# Base_IC.net
KiCad netlist of a schematic drawn in Altium Designer
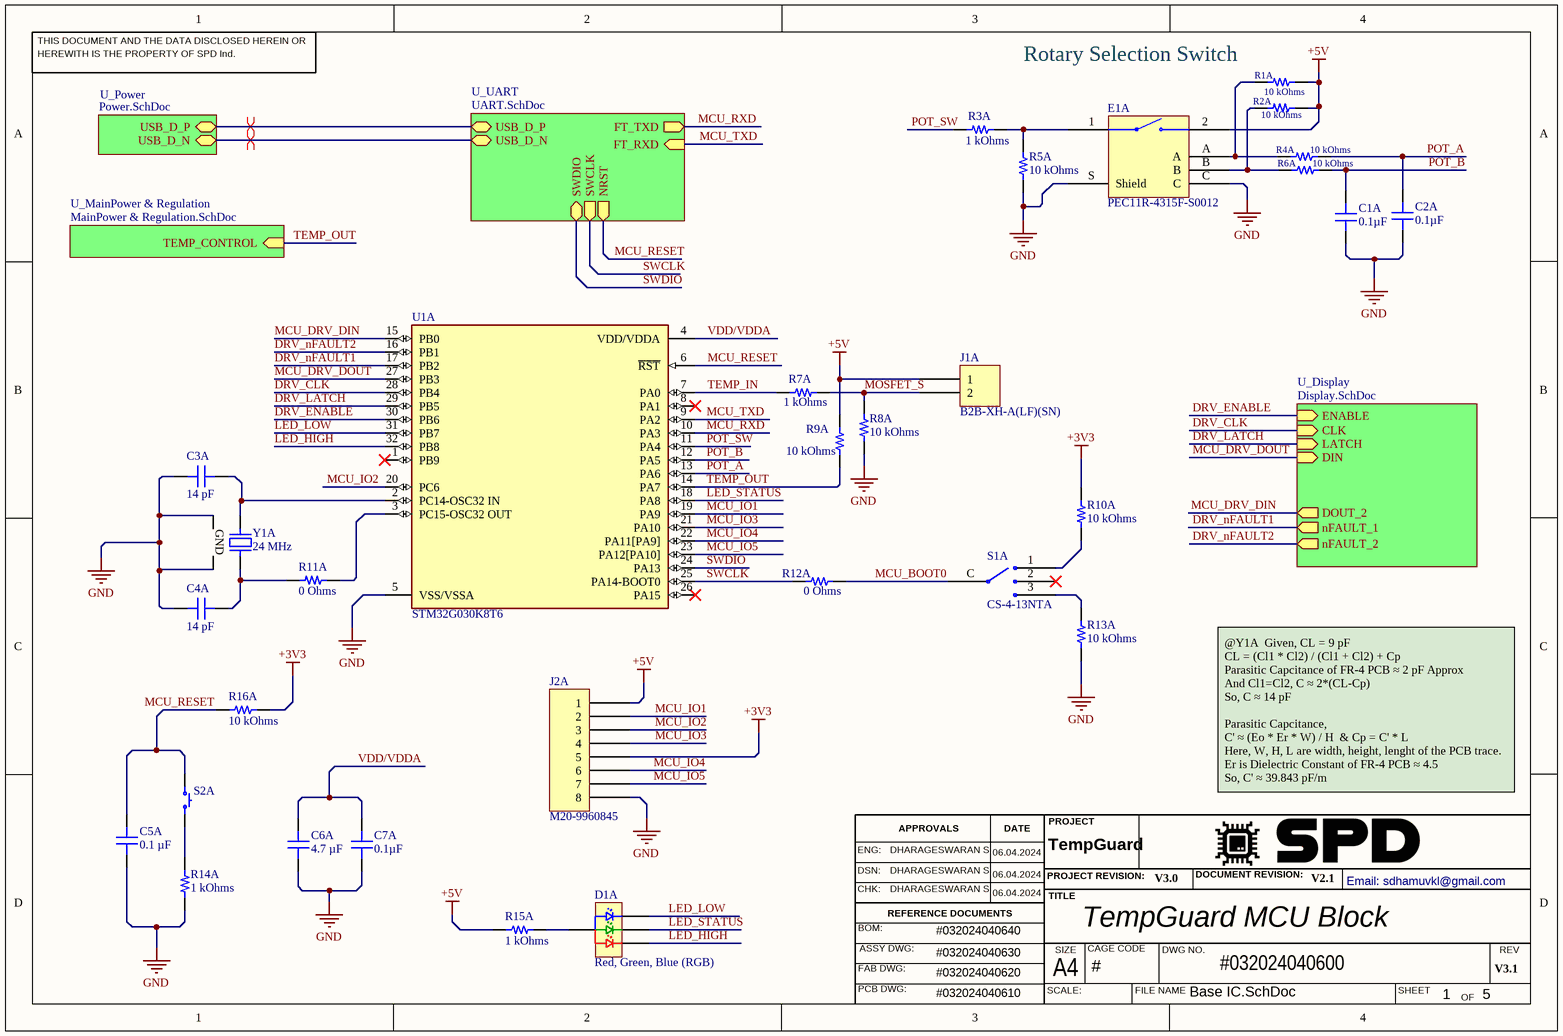
[diagram p0: Base IC.SchDoc]

(export (version "E")
  (design (tool "Eeschema 10.0.6"))
  (components
    (comp (ref "C1A")
      (value "0.1µF")
      (footprint "CAP 0402_1005")
      (description "CAP CER 0.1UF 10V X5R 0402")
      (fields (field (name "PART NUMBER") "LD02ZD104KAB2A") (field (name "MANUFACTURER") "AVX Corporation"))
      (libsource (lib "Postgres Altium Library - altium_library") (part "Capacitor"))
    )
    (comp (ref "C2A")
      (value "0.1µF")
      (footprint "CAP 0402_1005")
      (description "CAP CER 0.1UF 10V X5R 0402")
      (fields (field (name "PART NUMBER") "LD02ZD104KAB2A") (field (name "MANUFACTURER") "AVX Corporation"))
      (libsource (lib "Postgres Altium Library - altium_library") (part "Capacitor"))
    )
    (comp (ref "C3A")
      (value "14 pF")
      (footprint "CAP 0402_1005")
      (description "CAP CER 14PF 50V C0G/NP0 0402")
      (fields
        (field (name "PART NUMBER") "GJM1555C1H140FB01D")
        (field (name "MANUFACTURER") "Murata Electronics")
      )
      (libsource (lib "Postgres Altium Library - altium_library") (part "Capacitor"))
    )
    (comp (ref "C4A")
      (value "14 pF")
      (footprint "CAP 0402_1005")
      (description "CAP CER 14PF 50V C0G/NP0 0402")
      (fields
        (field (name "PART NUMBER") "GJM1555C1H140FB01D")
        (field (name "MANUFACTURER") "Murata Electronics")
      )
      (libsource (lib "Postgres Altium Library - altium_library") (part "Capacitor"))
    )
    (comp (ref "C5A")
      (value "0.1 µF")
      (footprint "CAP 0402_1005")
      (description "CAP CER 100NF 10V X7R 0402")
      (fields
        (field (name "PART NUMBER") "CL05B104KP5VPNC")
        (field (name "MANUFACTURER") "Samsung Electro-Mechanics")
      )
      (libsource (lib "Postgres Altium Library - altium_library") (part "Capacitor"))
    )
    (comp (ref "C6A")
      (value "4.7 µF")
      (footprint "CAP 0402_1005")
      (description "CAP CER 4.7UF 10V X6T 0402")
      (fields
        (field (name "PART NUMBER") "GRM155D81A475ME15D")
        (field (name "MANUFACTURER") "Murata Electronics")
      )
      (libsource (lib "Postgres Altium Library - altium_library") (part "Capacitor"))
    )
    (comp (ref "C7A")
      (value "0.1µF")
      (footprint "CAP 0402_1005")
      (description "CAP CER 0.1UF 10V X5R 0402")
      (fields (field (name "PART NUMBER") "LD02ZD104KAB2A") (field (name "MANUFACTURER") "AVX Corporation"))
      (libsource (lib "Postgres Altium Library - altium_library") (part "Capacitor"))
    )
    (comp (ref "D1A")
      (value "Red, Green, Blue (RGB)")
      (footprint "Harvatek B38G3RGB-10D0003H2U1930")
      (description "LED RGB MIXED WHITE ( 1.6(L)X1.6")
      (fields
        (field (name "PART NUMBER") "B38G3RGB-10D0003H2U1930")
        (field (name "MANUFACTURER") "Harvatek Corporation")
      )
      (libsource (lib "Postgres Altium Library - altium_library") (part "Harvatek B38G3RGB-10D0003H2U1930"))
    )
    (comp (ref "E1A")
      (value "PEC11R-4315F-S0012")
      (footprint "BOURNS PEC11R-4315F-S0012")
      (description "ROTARY ENCODER MECHANICAL 12PPR")
      (fields (field (name "MANUFACTURER") "Bourns Inc."))
      (libsource (lib "Postgres Altium Library - altium_library") (part "BOURNS PEC11R-4315F-S0012"))
    )
    (comp (ref "J1A")
      (value "B2B-XH-A(LF)(SN)")
      (footprint "JST XH B2B-XH-A")
      (description "CONN HEADER VERT 2POS 2.5MM")
      (fields (field (name "MANUFACTURER") "JST Sales America Inc."))
      (libsource (lib "Postgres Altium Library - altium_library") (part "2 Pin"))
    )
    (comp (ref "J2A")
      (value "M20-9960845")
      (footprint "HARWIN M20-9960845")
      (description "CONN HEADER R/A 8POS 2.54MM")
      (fields (field (name "MANUFACTURER") "Harwin Inc."))
      (libsource (lib "Postgres Altium Library - altium_library") (part "8 Pin"))
    )
    (comp (ref "R1A")
      (value "10 kOhms")
      (footprint "RES 0402_1005")
      (description "RES SMD 10K OHM 1% 1/16W 0402")
      (fields (field (name "PART NUMBER") "AA0402FR-0710KL") (field (name "TOLERANCE") "±1%"))
      (libsource (lib "Postgres Altium Library - altium_library") (part "Resistor"))
    )
    (comp (ref "R2A")
      (value "10 kOhms")
      (footprint "RES 0402_1005")
      (description "RES SMD 10K OHM 1% 1/16W 0402")
      (fields (field (name "PART NUMBER") "AA0402FR-0710KL") (field (name "TOLERANCE") "±1%"))
      (libsource (lib "Postgres Altium Library - altium_library") (part "Resistor"))
    )
    (comp (ref "R3A")
      (value "1 kOhms")
      (footprint "RES 0402_1005")
      (description "RES SMD 1K OHM 1% 1/16W 0402")
      (fields (field (name "PART NUMBER") "AA0402FR-071KL") (field (name "TOLERANCE") "±1%"))
      (libsource (lib "Postgres Altium Library - altium_library") (part "Resistor"))
    )
    (comp (ref "R4A")
      (value "10 kOhms")
      (footprint "RES 0402_1005")
      (description "RES SMD 10K OHM 1% 1/16W 0402")
      (fields (field (name "PART NUMBER") "AA0402FR-0710KL") (field (name "TOLERANCE") "±1%"))
      (libsource (lib "Postgres Altium Library - altium_library") (part "Resistor"))
    )
    (comp (ref "R5A")
      (value "10 kOhms")
      (footprint "RES 0402_1005")
      (description "RES SMD 10K OHM 1% 1/16W 0402")
      (fields (field (name "PART NUMBER") "AA0402FR-0710KL") (field (name "TOLERANCE") "±1%"))
      (libsource (lib "Postgres Altium Library - altium_library") (part "Resistor"))
    )
    (comp (ref "R6A")
      (value "10 kOhms")
      (footprint "RES 0402_1005")
      (description "RES SMD 10K OHM 1% 1/16W 0402")
      (fields (field (name "PART NUMBER") "AA0402FR-0710KL") (field (name "TOLERANCE") "±1%"))
      (libsource (lib "Postgres Altium Library - altium_library") (part "Resistor"))
    )
    (comp (ref "R7A")
      (value "1 kOhms")
      (footprint "RES 0402_1005")
      (description "RES SMD 1K OHM 1% 1/16W 0402")
      (fields (field (name "PART NUMBER") "AA0402FR-071KL") (field (name "TOLERANCE") "±1%"))
      (libsource (lib "Postgres Altium Library - altium_library") (part "Resistor"))
    )
    (comp (ref "R8A")
      (value "10 kOhms")
      (footprint "RES 0603_1608")
      (description "RES SMD 10K OHM 0.1% 1/10W 0603")
      (fields (field (name "PART NUMBER") "ERA-3AEB103V") (field (name "TOLERANCE") "±0.1%"))
      (libsource (lib "Postgres Altium Library - altium_library") (part "Resistor"))
    )
    (comp (ref "R9A")
      (value "10 kOhms")
      (footprint "RES 0603_1608")
      (description "RES SMD 10K OHM 0.1% 1/10W 0603")
      (fields (field (name "PART NUMBER") "ERA-3AEB103V") (field (name "TOLERANCE") "±0.1%"))
      (libsource (lib "Postgres Altium Library - altium_library") (part "Resistor"))
    )
    (comp (ref "R10A")
      (value "10 kOhms")
      (footprint "RES 0402_1005")
      (description "RES SMD 10K OHM 1% 1/16W 0402")
      (fields (field (name "PART NUMBER") "AA0402FR-0710KL") (field (name "TOLERANCE") "±1%"))
      (libsource (lib "Postgres Altium Library - altium_library") (part "Resistor"))
    )
    (comp (ref "R11A")
      (value "0 Ohms")
      (footprint "RES 0402_1005")
      (description "RES SMD 0 OHM JUMPER 1/16W 0402")
      (fields (field (name "PART NUMBER") "AC0402JR-070RL") (field (name "TOLERANCE") "Jumper"))
      (libsource (lib "Postgres Altium Library - altium_library") (part "Resistor"))
    )
    (comp (ref "R12A")
      (value "0 Ohms")
      (footprint "RES 0402_1005")
      (description "RES SMD 0 OHM JUMPER 1/16W 0402")
      (fields (field (name "PART NUMBER") "AC0402JR-070RL") (field (name "TOLERANCE") "Jumper"))
      (libsource (lib "Postgres Altium Library - altium_library") (part "Resistor"))
    )
    (comp (ref "R13A")
      (value "10 kOhms")
      (footprint "RES 0402_1005")
      (description "RES SMD 10K OHM 1% 1/16W 0402")
      (fields (field (name "PART NUMBER") "AA0402FR-0710KL") (field (name "TOLERANCE") "±1%"))
      (libsource (lib "Postgres Altium Library - altium_library") (part "Resistor"))
    )
    (comp (ref "R14A")
      (value "1 kOhms")
      (footprint "RES 0402_1005")
      (description "RES SMD 1K OHM 1% 1/16W 0402")
      (fields (field (name "PART NUMBER") "AA0402FR-071KL") (field (name "TOLERANCE") "±1%"))
      (libsource (lib "Postgres Altium Library - altium_library") (part "Resistor"))
    )
    (comp (ref "R15A")
      (value "1 kOhms")
      (footprint "RES 0603_1608")
      (description "RES 1K OHM 5% 1/10W 0603")
      (fields (field (name "PART NUMBER") "RMCF0603JT1K00") (field (name "TOLERANCE") "±5%"))
      (libsource (lib "Postgres Altium Library - altium_library") (part "Resistor"))
    )
    (comp (ref "R16A")
      (value "10 kOhms")
      (footprint "RES 0402_1005")
      (description "RES SMD 10K OHM 1% 1/16W 0402")
      (fields (field (name "PART NUMBER") "AA0402FR-0710KL") (field (name "TOLERANCE") "±1%"))
      (libsource (lib "Postgres Altium Library - altium_library") (part "Resistor"))
    )
    (comp (ref "S1A")
      (value "CS-4-13NTA")
      (footprint "NIDEC COPAL CS-4-13NTA")
      (description "SWITCH ROTARY DIP SP3T 100MA 16V")
      (fields (field (name "MANUFACTURER") "Nidec Copal Electronics"))
      (libsource (lib "Postgres Altium Library - altium_library") (part "NIDEC COPAL CS-4-13NTA"))
    )
    (comp (ref "S2A")
      (value "EVP-AWED4A")
      (footprint "PANASONIC EVPAW")
      (description "3.0MM X 2.0MM / 3.3N / 0.15MM ST")
      (fields (field (name "MANUFACTURER") "Panasonic Electronic Components"))
      (libsource (lib "Postgres Altium Library - altium_library") (part "SPST-NO 2 PIN"))
    )
    (comp (ref "U1A")
      (value "STM32G030K8T6")
      (footprint "FP-LQFP32-5V-IPC_A")
      (description "IC MCU 32BIT 64KB FLASH 32LQFP")
      (libsource (lib "Altium Content Vault") (part "fea91388a178aa646681c81fcef9c35"))
    )
    (comp (ref "Y1A")
      (value "24 MHz")
      (footprint "EPSON TSX-3225")
      (description "CRYSTAL 24.0000MHZ 9PF SMD")
      (fields (field (name "PART NUMBER") "TSX-3225 24.0000MF15X-AC3") (field (name "MANUFACTURER") "EPSON"))
      (libsource (lib "Postgres Altium Library - altium_library") (part "Epson Crystal TSX-3225"))
    )
  )
  (nets
    (net (code "1") (name "+3V3") (class "Default")
      (node (ref "J2A") (pin "5") (pinfunction "5_5") (pintype "passive"))
      (node (ref "R10A") (pin "2") (pinfunction "2_2") (pintype "passive"))
      (node (ref "R16A") (pin "1") (pinfunction "1_1") (pintype "passive"))
    )
    (net (code "2") (name "+5V") (class "Default")
      (node (ref "E1A") (pin "2") (pinfunction "2_2") (pintype "passive"))
      (node (ref "J1A") (pin "1") (pinfunction "1_1") (pintype "passive"))
      (node (ref "J2A") (pin "1") (pinfunction "1_1") (pintype "passive"))
      (node (ref "R15A") (pin "1") (pinfunction "1_1") (pintype "passive"))
      (node (ref "R1A") (pin "2") (pinfunction "2_2") (pintype "passive"))
      (node (ref "R2A") (pin "2") (pinfunction "2_2") (pintype "passive"))
      (node (ref "R9A") (pin "2") (pinfunction "2_2") (pintype "passive"))
    )
    (net (code "3") (name "/DRV_CLK") (class "Default")
      (node (ref "U1A") (pin "28") (pinfunction "PB4_28") (pintype "bidirectional"))
    )
    (net (code "4") (name "/DRV_ENABLE") (class "Default")
      (node (ref "U1A") (pin "30") (pinfunction "PB6_30") (pintype "bidirectional"))
    )
    (net (code "5") (name "/DRV_LATCH") (class "Default")
      (node (ref "U1A") (pin "29") (pinfunction "PB5_29") (pintype "bidirectional"))
    )
    (net (code "6") (name "/DRV_nFAULT1") (class "Default")
      (node (ref "U1A") (pin "17") (pinfunction "PB2_17") (pintype "bidirectional"))
    )
    (net (code "7") (name "/DRV_nFAULT2") (class "Default")
      (node (ref "U1A") (pin "16") (pinfunction "PB1_16") (pintype "bidirectional"))
    )
    (net (code "8") (name "/LED_HIGH") (class "Default")
      (node (ref "D1A") (pin "4") (pinfunction "RED_4") (pintype "passive"))
      (node (ref "U1A") (pin "32") (pinfunction "PB8_32") (pintype "bidirectional"))
    )
    (net (code "9") (name "/LED_LOW") (class "Default")
      (node (ref "D1A") (pin "2") (pinfunction "BLUE_2") (pintype "passive"))
      (node (ref "U1A") (pin "31") (pinfunction "PB7_31") (pintype "bidirectional"))
    )
    (net (code "10") (name "/LED_STATUS") (class "Default")
      (node (ref "D1A") (pin "1") (pinfunction "GREEN_1") (pintype "passive"))
      (node (ref "U1A") (pin "18") (pinfunction "PA8_18") (pintype "bidirectional"))
    )
    (net (code "11") (name "/MCU_BOOT0") (class "Default")
      (node (ref "R12A") (pin "2") (pinfunction "2_2") (pintype "passive"))
      (node (ref "S1A") (pin "C") (pinfunction "C_C") (pintype "passive"))
    )
    (net (code "12") (name "/MCU_DRV_DIN") (class "Default")
      (node (ref "U1A") (pin "15") (pinfunction "PB0_15") (pintype "bidirectional"))
    )
    (net (code "13") (name "/MCU_DRV_DOUT") (class "Default")
      (node (ref "U1A") (pin "27") (pinfunction "PB3_27") (pintype "bidirectional"))
    )
    (net (code "14") (name "/MCU_IO1") (class "Default")
      (node (ref "J2A") (pin "2") (pinfunction "2_2") (pintype "passive"))
      (node (ref "U1A") (pin "19") (pinfunction "PA9_19") (pintype "bidirectional"))
    )
    (net (code "15") (name "/MCU_IO2") (class "Default")
      (node (ref "J2A") (pin "3") (pinfunction "3_3") (pintype "passive"))
      (node (ref "U1A") (pin "20") (pinfunction "PC6_20") (pintype "bidirectional"))
    )
    (net (code "16") (name "/MCU_IO3") (class "Default")
      (node (ref "J2A") (pin "4") (pinfunction "4_4") (pintype "passive"))
      (node (ref "U1A") (pin "21") (pinfunction "PA10_21") (pintype "bidirectional"))
    )
    (net (code "17") (name "/MCU_IO4") (class "Default")
      (node (ref "J2A") (pin "6") (pinfunction "6_6") (pintype "passive"))
      (node (ref "U1A") (pin "22") (pinfunction "PA11[PA9]_22") (pintype "bidirectional"))
    )
    (net (code "18") (name "/MCU_IO5") (class "Default")
      (node (ref "J2A") (pin "7") (pinfunction "7_7") (pintype "passive"))
      (node (ref "U1A") (pin "23") (pinfunction "PA12[PA10]_23") (pintype "bidirectional"))
    )
    (net (code "19") (name "/MCU_RESET") (class "Default")
      (node (ref "C5A") (pin "2") (pinfunction "2_2") (pintype "passive"))
      (node (ref "R16A") (pin "2") (pinfunction "2_2") (pintype "passive"))
      (node (ref "S2A") (pin "1") (pinfunction "1_1") (pintype "passive"))
      (node (ref "U1A") (pin "6") (pinfunction "~{RST}_6") (pintype "input"))
    )
    (net (code "20") (name "/MCU_RXD") (class "Default")
      (node (ref "U1A") (pin "10") (pinfunction "PA3_10") (pintype "bidirectional"))
    )
    (net (code "21") (name "/MCU_TXD") (class "Default")
      (node (ref "U1A") (pin "9") (pinfunction "PA2_9") (pintype "bidirectional"))
    )
    (net (code "22") (name "/MOSFET_S") (class "Default")
      (node (ref "J1A") (pin "2") (pinfunction "2_2") (pintype "passive"))
      (node (ref "R7A") (pin "1") (pinfunction "1_1") (pintype "passive"))
      (node (ref "R8A") (pin "2") (pinfunction "2_2") (pintype "passive"))
    )
    (net (code "23") (name "/POT_A") (class "Default")
      (node (ref "C2A") (pin "2") (pinfunction "2_2") (pintype "passive"))
      (node (ref "R4A") (pin "1") (pinfunction "1_1") (pintype "passive"))
      (node (ref "U1A") (pin "13") (pinfunction "PA6_13") (pintype "bidirectional"))
    )
    (net (code "24") (name "/POT_B") (class "Default")
      (node (ref "C1A") (pin "2") (pinfunction "2_2") (pintype "passive"))
      (node (ref "R6A") (pin "1") (pinfunction "1_1") (pintype "passive"))
      (node (ref "U1A") (pin "12") (pinfunction "PA5_12") (pintype "bidirectional"))
    )
    (net (code "25") (name "/POT_SW") (class "Default")
      (node (ref "R3A") (pin "2") (pinfunction "2_2") (pintype "passive"))
      (node (ref "U1A") (pin "11") (pinfunction "PA4_11") (pintype "bidirectional"))
    )
    (net (code "26") (name "/SWCLK") (class "Default")
      (node (ref "R12A") (pin "1") (pinfunction "1_1") (pintype "passive"))
      (node (ref "U1A") (pin "25") (pinfunction "PA14-BOOT0_25") (pintype "bidirectional"))
    )
    (net (code "27") (name "/SWDIO") (class "Default")
      (node (ref "U1A") (pin "24") (pinfunction "PA13_24") (pintype "bidirectional"))
    )
    (net (code "28") (name "/TEMP_IN") (class "Default")
      (node (ref "R7A") (pin "2") (pinfunction "2_2") (pintype "passive"))
      (node (ref "U1A") (pin "7") (pinfunction "PA0_7") (pintype "bidirectional"))
    )
    (net (code "29") (name "/TEMP_OUT") (class "Default")
      (node (ref "R9A") (pin "1") (pinfunction "1_1") (pintype "passive"))
      (node (ref "U1A") (pin "14") (pinfunction "PA7_14") (pintype "bidirectional"))
    )
    (net (code "32") (name "/VDD{slash}VDDA") (class "Default")
      (node (ref "C6A") (pin "2") (pinfunction "2_2") (pintype "passive"))
      (node (ref "C7A") (pin "2") (pinfunction "2_2") (pintype "passive"))
      (node (ref "U1A") (pin "4") (pinfunction "VDD/VDDA_4") (pintype "power_in"))
    )
    (net (code "33") (name "GND") (class "Default")
      (node (ref "C1A") (pin "1") (pinfunction "1_1") (pintype "passive"))
      (node (ref "C2A") (pin "1") (pinfunction "1_1") (pintype "passive"))
      (node (ref "C3A") (pin "1") (pinfunction "1_1") (pintype "passive"))
      (node (ref "C4A") (pin "1") (pinfunction "1_1") (pintype "passive"))
      (node (ref "C5A") (pin "1") (pinfunction "1_1") (pintype "passive"))
      (node (ref "C6A") (pin "1") (pinfunction "1_1") (pintype "passive"))
      (node (ref "C7A") (pin "1") (pinfunction "1_1") (pintype "passive"))
      (node (ref "E1A") (pin "C") (pinfunction "C_C") (pintype "passive"))
      (node (ref "E1A") (pin "S") (pinfunction "Shield_S") (pintype "passive"))
      (node (ref "J2A") (pin "8") (pinfunction "8_8") (pintype "passive"))
      (node (ref "R13A") (pin "1") (pinfunction "1_1") (pintype "passive"))
      (node (ref "R14A") (pin "1") (pinfunction "1_1") (pintype "passive"))
      (node (ref "R5A") (pin "1") (pinfunction "1_1") (pintype "passive"))
      (node (ref "R8A") (pin "1") (pinfunction "1_1") (pintype "passive"))
      (node (ref "U1A") (pin "5") (pinfunction "VSS/VSSA_5") (pintype "power_in"))
      (node (ref "Y1A") (pin "2") (pinfunction "GND_2") (pintype "passive"))
      (node (ref "Y1A") (pin "4") (pinfunction "GND_4") (pintype "passive"))
    )
    (net (code "34") (name "Net-(C4A-Pad2)") (class "Default")
      (node (ref "C4A") (pin "2") (pinfunction "2_2") (pintype "passive"))
      (node (ref "R11A") (pin "1") (pinfunction "1_1") (pintype "passive"))
      (node (ref "Y1A") (pin "3") (pinfunction "3_3") (pintype "passive"))
    )
    (net (code "35") (name "Net-(D1A-ANODE)") (class "Default")
      (node (ref "D1A") (pin "3") (pinfunction "ANODE_3") (pintype "passive"))
      (node (ref "R15A") (pin "2") (pinfunction "2_2") (pintype "passive"))
    )
    (net (code "36") (name "Net-(E1A-Pad1)") (class "Default")
      (node (ref "E1A") (pin "1") (pinfunction "1_1") (pintype "passive"))
      (node (ref "R3A") (pin "1") (pinfunction "1_1") (pintype "passive"))
      (node (ref "R5A") (pin "2") (pinfunction "2_2") (pintype "passive"))
    )
    (net (code "37") (name "Net-(E1A-PadA)") (class "Default")
      (node (ref "E1A") (pin "A") (pinfunction "A_A") (pintype "passive"))
      (node (ref "R1A") (pin "1") (pinfunction "1_1") (pintype "passive"))
      (node (ref "R4A") (pin "2") (pinfunction "2_2") (pintype "passive"))
    )
    (net (code "38") (name "Net-(E1A-PadB)") (class "Default")
      (node (ref "E1A") (pin "B") (pinfunction "B_B") (pintype "passive"))
      (node (ref "R2A") (pin "1") (pinfunction "1_1") (pintype "passive"))
      (node (ref "R6A") (pin "2") (pinfunction "2_2") (pintype "passive"))
    )
    (net (code "39") (name "Net-(R10A-Pad1)") (class "Default")
      (node (ref "R10A") (pin "1") (pinfunction "1_1") (pintype "passive"))
      (node (ref "S1A") (pin "1") (pinfunction "1_1") (pintype "passive"))
    )
    (net (code "40") (name "Net-(R13A-Pad2)") (class "Default")
      (node (ref "R13A") (pin "2") (pinfunction "2_2") (pintype "passive"))
      (node (ref "S1A") (pin "3") (pinfunction "3_3") (pintype "passive"))
    )
    (net (code "41") (name "Net-(R14A-Pad2)") (class "Default")
      (node (ref "R14A") (pin "2") (pinfunction "2_2") (pintype "passive"))
      (node (ref "S2A") (pin "2") (pinfunction "2_2") (pintype "passive"))
    )
    (net (code "42") (name "Net-(U1A-PC14-OSC32_IN)") (class "Default")
      (node (ref "C3A") (pin "2") (pinfunction "2_2") (pintype "passive"))
      (node (ref "U1A") (pin "2") (pinfunction "PC14-OSC32_IN_2") (pintype "bidirectional"))
      (node (ref "Y1A") (pin "1") (pinfunction "1_1") (pintype "passive"))
    )
    (net (code "43") (name "Net-(U1A-PC15-OSC32_OUT)") (class "Default")
      (node (ref "R11A") (pin "2") (pinfunction "2_2") (pintype "passive"))
      (node (ref "U1A") (pin "3") (pinfunction "PC15-OSC32_OUT_3") (pintype "bidirectional"))
    )
    (net (code "44") (name "unconnected-(S1A-Pad2)") (class "Default")
      (node (ref "S1A") (pin "2") (pinfunction "2_2") (pintype "passive+no_connect"))
    )
    (net (code "45") (name "unconnected-(U1A-PA1-Pad8)") (class "Default")
      (node (ref "U1A") (pin "8") (pinfunction "PA1_8") (pintype "bidirectional+no_connect"))
    )
    (net (code "46") (name "unconnected-(U1A-PA15-Pad26)") (class "Default")
      (node (ref "U1A") (pin "26") (pinfunction "PA15_26") (pintype "bidirectional+no_connect"))
    )
    (net (code "47") (name "unconnected-(U1A-PB9-Pad1)") (class "Default")
      (node (ref "U1A") (pin "1") (pinfunction "PB9_1") (pintype "bidirectional+no_connect"))
    )
  )
)
